# Transceiver.net
KiCad netlist of a schematic drawn in EAGLE
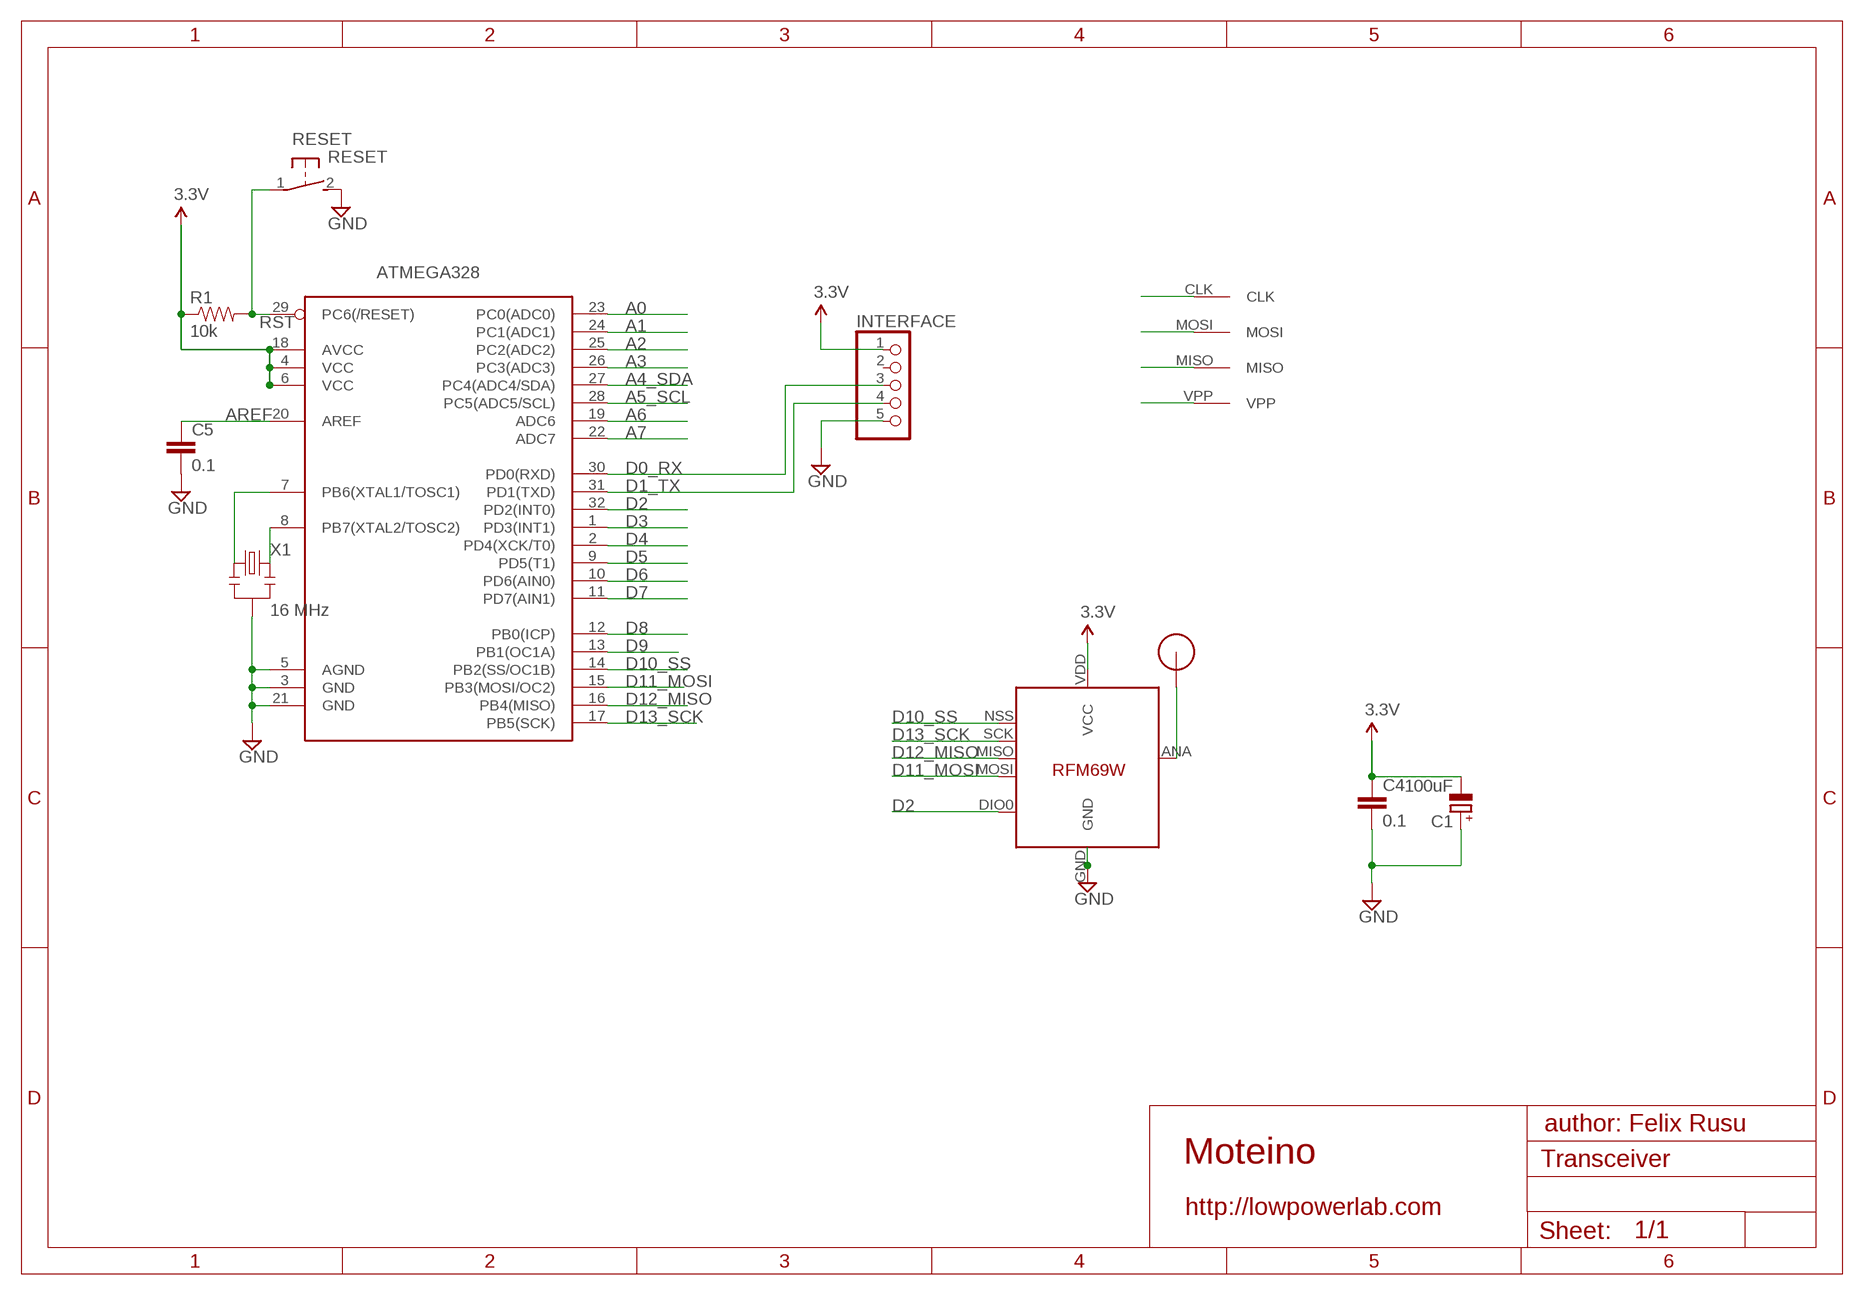
[diagram p0: schematic, sheet 1]

(export (version "E")
  (design (tool "Eeschema 10.0.6"))
  (components
    (comp (ref "ATMEGA328")
      (value "ATMega-328")
      (footprint "eagle-import:TQFP32-08")
      (libsource (lib "eagle-import") (part "ATMEGA168/328TQFP32"))
    )
    (comp (ref "C1")
      (value "100uF")
      (footprint "eagle-import:SMC_B")
      (libsource (lib "eagle-import") (part "CPOL-EUSMCB"))
    )
    (comp (ref "C4")
      (value "0.1")
      (footprint "eagle-import:0603-CAP")
      (libsource (lib "eagle-import") (part "CAP0603-CAP"))
    )
    (comp (ref "C5")
      (value "0.1")
      (footprint "eagle-import:0603-CAP")
      (libsource (lib "eagle-import") (part "CAP0603-CAP"))
    )
    (comp (ref "INTERFACE")
      (value "PINHD-1X5/90")
      (footprint "eagle-import:1X05_90")
      (libsource (lib "eagle-import") (part "PINHD-1X5/90"))
    )
    (comp (ref "R1")
      (value "10k")
      (footprint "eagle-import:0603-RES")
      (libsource (lib "eagle-import") (part "RESISTOR0603-RES"))
    )
    (comp (ref "RESET")
      (value "RESET")
      (footprint "eagle-import:DTSM-3")
      (libsource (lib "eagle-import") (part "DTSM-3"))
    )
    (comp (ref "U$1")
      (value "RFM12B_ANTENNA")
      (footprint "eagle-import:RFM12B-ANTENNA")
      (libsource (lib "eagle-import") (part "RFM12B_ANTENNA"))
    )
    (comp (ref "U$2")
      (value "AVRHEADERDIP")
      (footprint "eagle-import:AVRHEADER")
      (libsource (lib "eagle-import") (part "AVRHEADERDIP"))
    )
    (comp (ref "U$5")
      (value "RFM69")
      (footprint "eagle-import:RFM69W-MINPADS")
      (libsource (lib "eagle-import") (part "RFM69"))
    )
    (comp (ref "X1")
      (value "16 MHz")
      (footprint "eagle-import:RESONATOR-SMD")
      (libsource (lib "eagle-import") (part "RESONATORSMD"))
    )
  )
  (nets
    (net (code "1") (name "/A0") (class "Default")
      (node (ref "ATMEGA328") (pin "23") (pinfunction "PC0(ADC0)_23") (pintype "bidirectional"))
    )
    (net (code "2") (name "/A1") (class "Default")
      (node (ref "ATMEGA328") (pin "24") (pinfunction "PC1(ADC1)_24") (pintype "bidirectional"))
    )
    (net (code "3") (name "/A2") (class "Default")
      (node (ref "ATMEGA328") (pin "25") (pinfunction "PC2(ADC2)_25") (pintype "bidirectional"))
    )
    (net (code "4") (name "/A3") (class "Default")
      (node (ref "ATMEGA328") (pin "26") (pinfunction "PC3(ADC3)_26") (pintype "bidirectional"))
    )
    (net (code "5") (name "/A4_SDA") (class "Default")
      (node (ref "ATMEGA328") (pin "27") (pinfunction "PC4(ADC4/SDA)_27") (pintype "bidirectional"))
    )
    (net (code "6") (name "/A5_SCL") (class "Default")
      (node (ref "ATMEGA328") (pin "28") (pinfunction "PC5(ADC5/SCL)_28") (pintype "bidirectional"))
    )
    (net (code "7") (name "/A6") (class "Default")
      (node (ref "ATMEGA328") (pin "19") (pinfunction "ADC6_19") (pintype "bidirectional"))
    )
    (net (code "8") (name "/A7") (class "Default")
      (node (ref "ATMEGA328") (pin "22") (pinfunction "ADC7_22") (pintype "bidirectional"))
    )
    (net (code "9") (name "/AREF") (class "Default")
      (node (ref "ATMEGA328") (pin "20") (pinfunction "AREF_20") (pintype "bidirectional"))
      (node (ref "C5") (pin "1") (pinfunction "1_1") (pintype "passive"))
    )
    (net (code "10") (name "/D0_RX") (class "Default")
      (node (ref "ATMEGA328") (pin "30") (pinfunction "PD0(RXD)_30") (pintype "bidirectional"))
      (node (ref "INTERFACE") (pin "3") (pinfunction "3_3") (pintype "passive"))
    )
    (net (code "11") (name "/D1_TX") (class "Default")
      (node (ref "ATMEGA328") (pin "31") (pinfunction "PD1(TXD)_31") (pintype "bidirectional"))
      (node (ref "INTERFACE") (pin "4") (pinfunction "4_4") (pintype "passive"))
    )
    (net (code "12") (name "/D2") (class "Default")
      (node (ref "ATMEGA328") (pin "32") (pinfunction "PD2(INT0)_32") (pintype "bidirectional"))
      (node (ref "U$5") (pin "DIO0") (pinfunction "DIO0_DIO0") (pintype "open_collector"))
    )
    (net (code "13") (name "/D3") (class "Default")
      (node (ref "ATMEGA328") (pin "1") (pinfunction "PD3(INT1)_1") (pintype "bidirectional"))
    )
    (net (code "14") (name "/D4") (class "Default")
      (node (ref "ATMEGA328") (pin "2") (pinfunction "PD4(XCK/T0)_2") (pintype "bidirectional"))
    )
    (net (code "15") (name "/D5") (class "Default")
      (node (ref "ATMEGA328") (pin "9") (pinfunction "PD5(T1)_9") (pintype "bidirectional"))
    )
    (net (code "16") (name "/D6") (class "Default")
      (node (ref "ATMEGA328") (pin "10") (pinfunction "PD6(AIN0)_10") (pintype "bidirectional"))
    )
    (net (code "17") (name "/D7") (class "Default")
      (node (ref "ATMEGA328") (pin "11") (pinfunction "PD7(AIN1)_11") (pintype "bidirectional"))
    )
    (net (code "18") (name "/D8") (class "Default")
      (node (ref "ATMEGA328") (pin "12") (pinfunction "PB0(ICP)_12") (pintype "bidirectional"))
    )
    (net (code "19") (name "/D9") (class "Default")
      (node (ref "ATMEGA328") (pin "13") (pinfunction "PB1(OC1A)_13") (pintype "bidirectional"))
    )
    (net (code "20") (name "/D10_SS") (class "Default")
      (node (ref "ATMEGA328") (pin "14") (pinfunction "PB2(SS/OC1B)_14") (pintype "bidirectional"))
      (node (ref "U$5") (pin "NSS") (pinfunction "SEL_NSS") (pintype "input"))
    )
    (net (code "21") (name "/D11_MOSI") (class "Default")
      (node (ref "ATMEGA328") (pin "15") (pinfunction "PB3(MOSI/OC2)_15") (pintype "bidirectional"))
      (node (ref "U$2") (pin "MOSI") (pinfunction "MOSI_MOSI") (pintype "bidirectional"))
      (node (ref "U$5") (pin "MOSI") (pinfunction "MOSI_MOSI") (pintype "output"))
    )
    (net (code "22") (name "/D12_MISO") (class "Default")
      (node (ref "ATMEGA328") (pin "16") (pinfunction "PB4(MISO)_16") (pintype "bidirectional"))
      (node (ref "U$2") (pin "MISO") (pinfunction "MISO_MISO") (pintype "bidirectional"))
      (node (ref "U$5") (pin "MISO") (pinfunction "MISO_MISO") (pintype "input"))
    )
    (net (code "23") (name "/D13_SCK") (class "Default")
      (node (ref "ATMEGA328") (pin "17") (pinfunction "PB5(SCK)_17") (pintype "bidirectional"))
      (node (ref "U$2") (pin "CLK") (pinfunction "CLK_CLK") (pintype "bidirectional"))
      (node (ref "U$5") (pin "SCK") (pinfunction "SCK_SCK") (pintype "input"))
    )
    (net (code "24") (name "/RST") (class "Default")
      (node (ref "ATMEGA328") (pin "29") (pinfunction "PC6(/RESET)_29") (pintype "bidirectional"))
      (node (ref "R1") (pin "2") (pinfunction "2_2") (pintype "passive"))
      (node (ref "RESET") (pin "1") (pinfunction "1_1") (pintype "passive"))
      (node (ref "U$2") (pin "VPP") (pinfunction "VPP_VPP") (pintype "bidirectional"))
    )
    (net (code "25") (name "3.3V") (class "Default")
      (node (ref "ATMEGA328") (pin "18") (pinfunction "AVCC_18") (pintype "bidirectional"))
      (node (ref "ATMEGA328") (pin "4") (pinfunction "VCC_4") (pintype "bidirectional"))
      (node (ref "ATMEGA328") (pin "6") (pinfunction "VCC_6") (pintype "bidirectional"))
      (node (ref "C1") (pin "-") (pinfunction "-_-") (pintype "passive"))
      (node (ref "C4") (pin "1") (pinfunction "1_1") (pintype "passive"))
      (node (ref "INTERFACE") (pin "1") (pinfunction "1_1") (pintype "passive"))
      (node (ref "R1") (pin "1") (pinfunction "1_1") (pintype "passive"))
      (node (ref "U$5") (pin "VDD") (pinfunction "VCC_VDD") (pintype "power_in"))
    )
    (net (code "26") (name "GND") (class "Default")
      (node (ref "ATMEGA328") (pin "21") (pinfunction "GND_21") (pintype "bidirectional"))
      (node (ref "ATMEGA328") (pin "3") (pinfunction "GND_3") (pintype "bidirectional"))
      (node (ref "ATMEGA328") (pin "5") (pinfunction "AGND_5") (pintype "bidirectional"))
      (node (ref "C1") (pin "+") (pinfunction "+_+") (pintype "passive"))
      (node (ref "C4") (pin "2") (pinfunction "2_2") (pintype "passive"))
      (node (ref "C5") (pin "2") (pinfunction "2_2") (pintype "passive"))
      (node (ref "INTERFACE") (pin "5") (pinfunction "5_5") (pintype "passive"))
      (node (ref "RESET") (pin "2") (pinfunction "2_2") (pintype "passive"))
      (node (ref "U$5") (pin "GND") (pinfunction "GND_GND") (pintype "power_in"))
      (node (ref "X1") (pin "2") (pinfunction "2_2") (pintype "passive"))
    )
    (net (code "27") (name "Net-(ATMEGA328-PB6(XTAL1{slash}TOSC1))") (class "Default")
      (node (ref "ATMEGA328") (pin "7") (pinfunction "PB6(XTAL1/TOSC1)_7") (pintype "bidirectional"))
      (node (ref "X1") (pin "1") (pinfunction "1_1") (pintype "passive"))
    )
    (net (code "28") (name "Net-(ATMEGA328-PB7(XTAL2{slash}TOSC2))") (class "Default")
      (node (ref "ATMEGA328") (pin "8") (pinfunction "PB7(XTAL2/TOSC2)_8") (pintype "bidirectional"))
      (node (ref "X1") (pin "3") (pinfunction "3_3") (pintype "passive"))
    )
    (net (code "29") (name "Net-(U$1-1)") (class "Default")
      (node (ref "U$1") (pin "P$1") (pinfunction "1_P$1") (pintype "bidirectional"))
      (node (ref "U$5") (pin "ANA") (pinfunction "ANT_ANA") (pintype "passive"))
    )
    (net (code "30") (name "unconnected-(INTERFACE-Pad2)") (class "Default")
      (node (ref "INTERFACE") (pin "2") (pinfunction "2_2") (pintype "passive"))
    )
  )
)
